# FE_Channel.net
KiCad netlist of a schematic drawn in Altium Designer
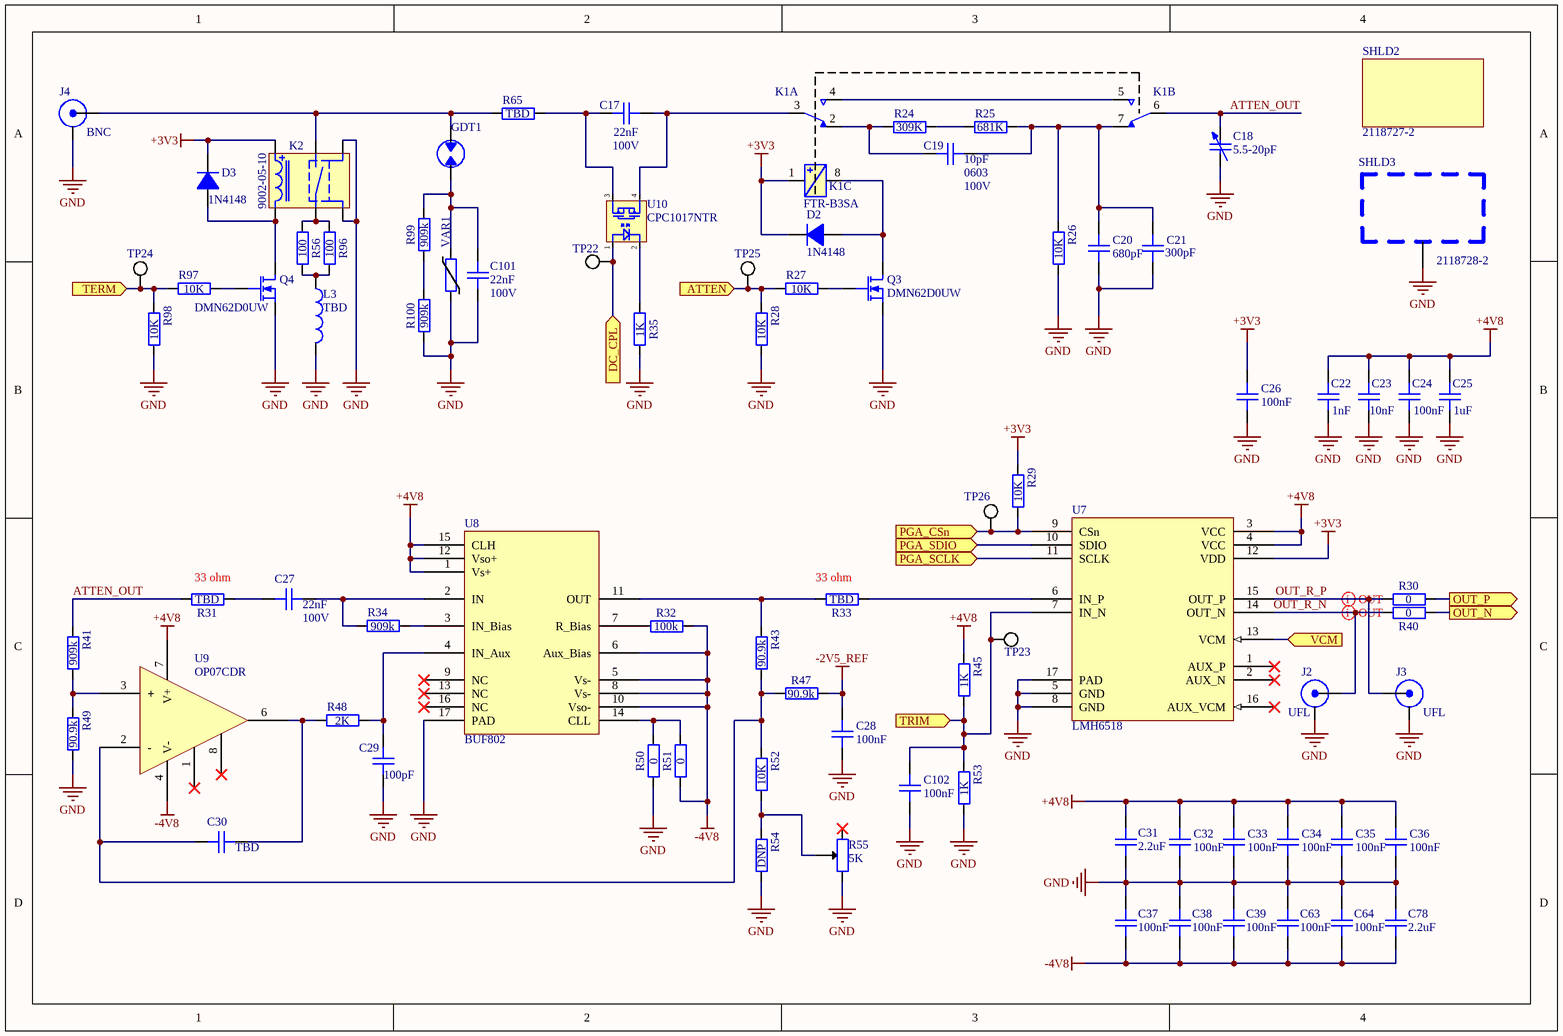
[diagram p0: FE_Channel.SchDoc]

(export (version "E")
  (design (tool "Eeschema 10.0.6"))
  (components
    (comp (ref "C17")
      (value "22nF")
      (footprint "GEN_C_0603")
      (fields (field (name "VOLTAGE RATING") "100V"))
      (libsource (lib "DSO") (part "CAP 22nF 100V X7R 0603"))
    )
    (comp (ref "C18")
      (value "5.5-20pF")
      (footprint "EW_TRIMCAP")
      (libsource (lib "DSO") (part "CAP TRIMMER 5.5-20PF 500V"))
    )
    (comp (ref "C19")
      (value "10pF")
      (footprint "GEN_C_0603")
      (fields (field (name "PACKAGE") "0603") (field (name "VOLTAGE RATING") "100V"))
      (libsource (lib "DSO") (part "CAP 10pF 100V C0G 0603"))
    )
    (comp (ref "C20")
      (value "680pF")
      (footprint "GEN_C_0402")
      (libsource (lib "DSO") (part "CAP 680pF 50V C0G 0402"))
    )
    (comp (ref "C21")
      (value "300pF")
      (footprint "GEN_C_0402")
      (libsource (lib "DSO") (part "CAP 300pF 50V C0G 0402"))
    )
    (comp (ref "C22")
      (value "1nF")
      (footprint "GEN_C_0402")
      (libsource (lib "DSO") (part "CAP 1nF 50V C0G 0402"))
    )
    (comp (ref "C23")
      (value "10nF")
      (footprint "GEN_C_0402")
      (libsource (lib "DSO") (part "CAP 10nF 50V X7R 0402"))
    )
    (comp (ref "C24")
      (value "100nF")
      (footprint "GEN_C_0402")
      (libsource (lib "DSO") (part "CAP 100nF 16V X7R 0402"))
    )
    (comp (ref "C25")
      (value "1uF")
      (footprint "GEN_C_0402")
      (libsource (lib "DSO") (part "CAP 1uF 25V X5R 0402"))
    )
    (comp (ref "C26")
      (value "100nF")
      (footprint "GEN_C_0402")
      (libsource (lib "DSO") (part "CAP 100nF 16V X7R 0402"))
    )
    (comp (ref "C27")
      (value "22nF")
      (footprint "GEN_C_0603")
      (fields (field (name "VOLTAGE RATING") "100V"))
      (libsource (lib "DSO") (part "CAP 22nF 100V X7R 0603"))
    )
    (comp (ref "C28")
      (value "100nF")
      (footprint "GEN_C_0402")
      (libsource (lib "DSO") (part "CAP 100nF 16V X7R 0402"))
    )
    (comp (ref "C29")
      (value "100pF")
      (footprint "GEN_C_0402")
      (libsource (lib "DSO") (part "CAP 100pF 50V C0G 0402"))
    )
    (comp (ref "C30") (value "TBD") (footprint "GEN_C_0402") (libsource (lib "DSO") (part "CAP TBD 0402")))
    (comp (ref "C31")
      (value "2.2uF")
      (footprint "GEN_C_0402")
      (libsource (lib "DSO") (part "CAP 2.2uF 10V X5R 0402"))
    )
    (comp (ref "C32")
      (value "100nF")
      (footprint "GEN_C_0402")
      (libsource (lib "DSO") (part "CAP 100nF 16V X7R 0402"))
    )
    (comp (ref "C33")
      (value "100nF")
      (footprint "GEN_C_0402")
      (libsource (lib "DSO") (part "CAP 100nF 16V X7R 0402"))
    )
    (comp (ref "C34")
      (value "100nF")
      (footprint "GEN_C_0402")
      (libsource (lib "DSO") (part "CAP 100nF 16V X7R 0402"))
    )
    (comp (ref "C35")
      (value "100nF")
      (footprint "GEN_C_0402")
      (libsource (lib "DSO") (part "CAP 100nF 16V X7R 0402"))
    )
    (comp (ref "C36")
      (value "100nF")
      (footprint "GEN_C_0402")
      (libsource (lib "DSO") (part "CAP 100nF 16V X7R 0402"))
    )
    (comp (ref "C37")
      (value "100nF")
      (footprint "GEN_C_0402")
      (libsource (lib "DSO") (part "CAP 100nF 16V X7R 0402"))
    )
    (comp (ref "C38")
      (value "100nF")
      (footprint "GEN_C_0402")
      (libsource (lib "DSO") (part "CAP 100nF 16V X7R 0402"))
    )
    (comp (ref "C39")
      (value "100nF")
      (footprint "GEN_C_0402")
      (libsource (lib "DSO") (part "CAP 100nF 16V X7R 0402"))
    )
    (comp (ref "C63")
      (value "100nF")
      (footprint "GEN_C_0402")
      (libsource (lib "DSO") (part "CAP 100nF 16V X7R 0402"))
    )
    (comp (ref "C64")
      (value "100nF")
      (footprint "GEN_C_0402")
      (libsource (lib "DSO") (part "CAP 100nF 16V X7R 0402"))
    )
    (comp (ref "C78")
      (value "2.2uF")
      (footprint "GEN_C_0402")
      (libsource (lib "DSO") (part "CAP 2.2uF 10V X5R 0402"))
    )
    (comp (ref "C101")
      (value "22nF")
      (footprint "GEN_C_0603")
      (fields (field (name "VOLTAGE RATING") "100V"))
      (libsource (lib "DSO") (part "CAP 22nF 100V X7R 0603"))
    )
    (comp (ref "C102")
      (value "100nF")
      (footprint "GEN_C_0402")
      (libsource (lib "DSO") (part "CAP 100nF 16V X7R 0402"))
    )
    (comp (ref "D2") (value "1N4148") (footprint "GEN_SOD_323") (libsource (lib "DSO") (part "DIODE 1N4148")))
    (comp (ref "D3") (value "1N4148") (footprint "GEN_SOD_323") (libsource (lib "DSO") (part "DIODE 1N4148")))
    (comp (ref "GDT1")
      (value "4532-075-LF")
      (footprint "BOU_2051")
      (libsource (lib "DSO") (part "GDT 75V 1812"))
    )
    (comp (ref "J2") (value "UFL") (footprint "TE_2334884-1") (libsource (lib "DSO") (part "UFL Jack SMD")))
    (comp (ref "J3") (value "UFL") (footprint "TE_2334884-1") (libsource (lib "DSO") (part "UFL Jack SMD")))
    (comp (ref "J4") (value "BNC") (footprint "MOL_0731000105") (libsource (lib "DSO") (part "BNC JACK R/A")))
    (comp (ref "K1")
      (value "FTR-B3SA")
      (footprint "FUJ_FTR-B3SA")
      (libsource (lib "") (part "RELAY DPDT-NO FTR-B3SA_1"))
    )
    (comp (ref "K2")
      (value "9002-05-10")
      (footprint "COTO_9002-05-10")
      (libsource (lib "DSO") (part "RELAY RF SPST-NO 9002-05-10"))
    )
    (comp (ref "L3") (value "TBD") (footprint "GEN_L_0402") (libsource (lib "DSO") (part "IND TBD 0402")))
    (comp (ref "Q3")
      (value "DMN62D0UW")
      (footprint "GEN_SOT_323")
      (libsource (lib "DSO") (part "NMOS DMN62D0UW"))
    )
    (comp (ref "Q4")
      (value "DMN62D0UW")
      (footprint "GEN_SOT_323")
      (libsource (lib "DSO") (part "NMOS DMN62D0UW"))
    )
    (comp (ref "R24")
      (value "309K")
      (footprint "GEN_R_0402")
      (fields (field (name "TOLERANCE") "1%"))
      (libsource (lib "DSO") (part "RES 309K OHM 1% 1/16W 0402"))
    )
    (comp (ref "R25")
      (value "681K")
      (footprint "GEN_R_0402")
      (fields (field (name "TOLERANCE") "1%"))
      (libsource (lib "DSO") (part "RES 681K OHM 1% 1/16W 0402"))
    )
    (comp (ref "R26")
      (value "10K")
      (footprint "GEN_R_0402")
      (fields (field (name "TOLERANCE") "1%"))
      (libsource (lib "DSO") (part "RES 10K OHM 1% 1/10W 0402"))
    )
    (comp (ref "R27")
      (value "10K")
      (footprint "GEN_R_0402")
      (fields (field (name "TOLERANCE") "1%"))
      (libsource (lib "") (part "RES 10K OHM 1% 1/10W 0402_1"))
    )
    (comp (ref "R28")
      (value "10K")
      (footprint "GEN_R_0402")
      (fields (field (name "TOLERANCE") "1%"))
      (libsource (lib "DSO") (part "RES 10K OHM 1% 1/10W 0402"))
    )
    (comp (ref "R29")
      (value "10K")
      (footprint "GEN_R_0402")
      (fields (field (name "TOLERANCE") "1%"))
      (libsource (lib "DSO") (part "RES 10K OHM 1% 1/10W 0402"))
    )
    (comp (ref "R30")
      (value "0")
      (footprint "GEN_R_0402")
      (libsource (lib "DSO") (part "RES 0 OHM 1/16W 0402"))
    )
    (comp (ref "R31")
      (value "TBD")
      (footprint "GEN_R_0402")
      (fields (field (name "TOLERANCE") "1%"))
      (libsource (lib "DSO") (part "RES TBD 0402"))
    )
    (comp (ref "R32")
      (value "100k")
      (footprint "GEN_R_0402")
      (fields (field (name "TOLERANCE") "1%"))
      (libsource (lib "DSO") (part "RES 100K OHM 1% 1/10W 0402"))
    )
    (comp (ref "R33")
      (value "TBD")
      (footprint "GEN_R_0402")
      (fields (field (name "TOLERANCE") "1%"))
      (libsource (lib "DSO") (part "RES TBD 0402"))
    )
    (comp (ref "R34")
      (value "909k")
      (footprint "GEN_R_0402")
      (fields (field (name "TOLERANCE") "1%"))
      (libsource (lib "") (part "RES 909K OHM 1% 1/16W 0402_1"))
    )
    (comp (ref "R35")
      (value "1K")
      (footprint "GEN_R_0402")
      (fields (field (name "TOLERANCE") "1%"))
      (libsource (lib "DSO") (part "RES 1K OHM 1% 1/10W 0402"))
    )
    (comp (ref "R40")
      (value "0")
      (footprint "GEN_R_0402")
      (libsource (lib "DSO") (part "RES 0 OHM 1/16W 0402"))
    )
    (comp (ref "R41")
      (value "909k")
      (footprint "GEN_R_0402")
      (fields (field (name "TOLERANCE") "1%"))
      (libsource (lib "DSO") (part "RES 909K OHM 1% 1/16W 0402"))
    )
    (comp (ref "R43")
      (value "90.9k")
      (footprint "GEN_R_0402")
      (fields (field (name "TOLERANCE") "1%"))
      (libsource (lib "") (part "RES 90.9K OHM 1% 1/16W 0402_1"))
    )
    (comp (ref "R45")
      (value "1K")
      (footprint "GEN_R_0402")
      (fields (field (name "TOLERANCE") "1%"))
      (libsource (lib "") (part "RES 1K OHM 1% 1/10W 0402_1"))
    )
    (comp (ref "R47")
      (value "90.9k")
      (footprint "GEN_R_0402")
      (fields (field (name "TOLERANCE") "1%"))
      (libsource (lib "DSO") (part "RES 90.9K OHM 1% 1/16W 0402"))
    )
    (comp (ref "R48")
      (value "2K")
      (footprint "GEN_R_0402")
      (fields (field (name "TOLERANCE") "1%"))
      (libsource (lib "DSO") (part "RES 2K OHM 1% 1/16W 0402"))
    )
    (comp (ref "R49")
      (value "90.9k")
      (footprint "GEN_R_0402")
      (fields (field (name "TOLERANCE") "1%"))
      (libsource (lib "") (part "RES 90.9K OHM 1% 1/16W 0402_1"))
    )
    (comp (ref "R50")
      (value "0")
      (footprint "GEN_R_0402")
      (libsource (lib "") (part "RES 0 OHM 1/16W 0402_1"))
    )
    (comp (ref "R51")
      (value "0")
      (footprint "GEN_R_0402")
      (libsource (lib "") (part "RES 0 OHM 1/16W 0402_1"))
    )
    (comp (ref "R52")
      (value "10K")
      (footprint "GEN_R_0402")
      (fields (field (name "TOLERANCE") "1%"))
      (libsource (lib "DSO") (part "RES 10K OHM 1% 1/10W 0402"))
    )
    (comp (ref "R53")
      (value "1K")
      (footprint "GEN_R_0402")
      (fields (field (name "TOLERANCE") "1%"))
      (libsource (lib "") (part "RES 1K OHM 1% 1/10W 0402_1"))
    )
    (comp (ref "R54")
      (value "DNP")
      (footprint "GEN_R_0402")
      (fields (field (name "TOLERANCE") "1%"))
      (libsource (lib "DSO") (part "RES DNP 0402"))
    )
    (comp (ref "R55")
      (value "5K")
      (footprint "BOU_3mm_POT")
      (fields (field (name "TOLERANCE") "1%"))
      (libsource (lib "DSO") (part "TRIMMER 5K OHM 0.1W J LEAD TOP"))
    )
    (comp (ref "R56")
      (value "100")
      (footprint "GEN_R_0402")
      (fields (field (name "TOLERANCE") "1%"))
      (libsource (lib "DSO") (part "RES 100 OHM 1% 1/10W 0402"))
    )
    (comp (ref "R65") (value "TBD") (footprint "GEN_R_0603") (libsource (lib "DSO") (part "RES TBD 0603")))
    (comp (ref "R96")
      (value "100")
      (footprint "GEN_R_0402")
      (fields (field (name "TOLERANCE") "1%"))
      (libsource (lib "DSO") (part "RES 100 OHM 1% 1/10W 0402"))
    )
    (comp (ref "R97")
      (value "10K")
      (footprint "GEN_R_0402")
      (fields (field (name "TOLERANCE") "1%"))
      (libsource (lib "") (part "RES 10K OHM 1% 1/10W 0402_1"))
    )
    (comp (ref "R98")
      (value "10K")
      (footprint "GEN_R_0402")
      (fields (field (name "TOLERANCE") "1%"))
      (libsource (lib "DSO") (part "RES 10K OHM 1% 1/10W 0402"))
    )
    (comp (ref "R99")
      (value "909k")
      (footprint "GEN_R_0402")
      (fields (field (name "TOLERANCE") "1%"))
      (libsource (lib "DSO") (part "RES 909K OHM 1% 1/16W 0402"))
    )
    (comp (ref "R100")
      (value "909k")
      (footprint "GEN_R_0402")
      (fields (field (name "TOLERANCE") "1%"))
      (libsource (lib "DSO") (part "RES 909K OHM 1% 1/16W 0402"))
    )
    (comp (ref "SHLD2") (value "2118727-2") (libsource (lib "DSO") (part "SHIELD 2118727-2")))
    (comp (ref "SHLD3")
      (value "2118728-2")
      (footprint "TE_2118728-2")
      (libsource (lib "DSO") (part "SHIELD 2118728-2"))
    )
    (comp (ref "TP22") (value "PCB") (footprint "GEN_TP_PCB") (libsource (lib "DSO") (part "TP PCB 1mm")))
    (comp (ref "TP23") (value "PCB") (footprint "GEN_TP_PCB") (libsource (lib "DSO") (part "TP PCB 1mm")))
    (comp (ref "TP24") (value "PCB") (footprint "GEN_TP_PCB") (libsource (lib "DSO") (part "TP PCB 1mm")))
    (comp (ref "TP25") (value "PCB") (footprint "GEN_TP_PCB") (libsource (lib "DSO") (part "TP PCB 1mm")))
    (comp (ref "TP26") (value "PCB") (footprint "GEN_TP_PCB") (libsource (lib "DSO") (part "TP PCB 1mm")))
    (comp (ref "U7")
      (value "LMH6518")
      (footprint "TI_WQFN_RGH0016A")
      (libsource (lib "DSO") (part "IC PGA LMH6518"))
    )
    (comp (ref "U8")
      (value "BUF802")
      (footprint "TI_VQFN_RGT0016C")
      (libsource (lib "DSO") (part "IC BUFFER AMP BUF802"))
    )
    (comp (ref "U9")
      (value "OP07CDR")
      (footprint "TI_SOIC8_D0008A")
      (libsource (lib "DSO") (part "IC OPAMP OP07CDR"))
    )
    (comp (ref "U10")
      (value "CPC1017NTR")
      (footprint "IXY_CPC1017")
      (libsource (lib "DSO") (part "SSR CPC1017NTR"))
    )
    (comp (ref "VAR1")
      (value "ZV40K1210251NIR1HT")
      (footprint "GEN_VAR_1210")
      (libsource (lib "DSO") (part "VARISTOR 68V 250A 1210"))
    )
  )
  (nets
    (net (code "1") (name "+3V3") (class "Default")
      (node (ref "C26") (pin "2") (pinfunction "2_2") (pintype "passive"))
      (node (ref "D2") (pin "1") (pinfunction "K_1") (pintype "passive"))
      (node (ref "D3") (pin "1") (pinfunction "K_1") (pintype "passive"))
      (node (ref "K1") (pin "1") (pinfunction "1_1") (pintype "passive"))
      (node (ref "K2") (pin "2") (pinfunction "2_2") (pintype "passive"))
      (node (ref "R29") (pin "2") (pinfunction "2_2") (pintype "passive"))
      (node (ref "U7") (pin "12") (pinfunction "VDD_12") (pintype "power_in"))
    )
    (net (code "2") (name "+4V8") (class "Default")
      (node (ref "C22") (pin "2") (pinfunction "2_2") (pintype "passive"))
      (node (ref "C23") (pin "2") (pinfunction "2_2") (pintype "passive"))
      (node (ref "C24") (pin "2") (pinfunction "2_2") (pintype "passive"))
      (node (ref "C25") (pin "2") (pinfunction "2_2") (pintype "passive"))
      (node (ref "C31") (pin "2") (pinfunction "2_2") (pintype "passive"))
      (node (ref "C32") (pin "1") (pinfunction "1_1") (pintype "passive"))
      (node (ref "C33") (pin "1") (pinfunction "1_1") (pintype "passive"))
      (node (ref "C34") (pin "1") (pinfunction "1_1") (pintype "passive"))
      (node (ref "C35") (pin "2") (pinfunction "2_2") (pintype "passive"))
      (node (ref "C36") (pin "2") (pinfunction "2_2") (pintype "passive"))
      (node (ref "R45") (pin "2") (pinfunction "2_2") (pintype "passive"))
      (node (ref "U7") (pin "3") (pinfunction "VCC_3") (pintype "power_in"))
      (node (ref "U7") (pin "4") (pinfunction "VCC_4") (pintype "power_in"))
      (node (ref "U8") (pin "1") (pinfunction "Vs+_1") (pintype "passive"))
      (node (ref "U8") (pin "12") (pinfunction "Vso+_12") (pintype "passive"))
      (node (ref "U8") (pin "15") (pinfunction "CLH_15") (pintype "passive"))
      (node (ref "U9") (pin "7") (pinfunction "V+_7") (pintype "passive"))
    )
    (net (code "3") (name "-2V5_REF") (class "Default")
      (node (ref "C28") (pin "1") (pinfunction "1_1") (pintype "passive"))
      (node (ref "R47") (pin "1") (pinfunction "1_1") (pintype "passive"))
    )
    (net (code "4") (name "-4V8") (class "Default")
      (node (ref "C37") (pin "2") (pinfunction "2_2") (pintype "passive"))
      (node (ref "C38") (pin "2") (pinfunction "2_2") (pintype "passive"))
      (node (ref "C39") (pin "1") (pinfunction "1_1") (pintype "passive"))
      (node (ref "C63") (pin "1") (pinfunction "1_1") (pintype "passive"))
      (node (ref "C64") (pin "1") (pinfunction "1_1") (pintype "passive"))
      (node (ref "C78") (pin "2") (pinfunction "2_2") (pintype "passive"))
      (node (ref "R32") (pin "2") (pinfunction "2_2") (pintype "passive"))
      (node (ref "R51") (pin "1") (pinfunction "1_1") (pintype "passive"))
      (node (ref "U8") (pin "10") (pinfunction "Vso-_10") (pintype "passive"))
      (node (ref "U8") (pin "5") (pinfunction "Vs-_5") (pintype "passive"))
      (node (ref "U8") (pin "6") (pinfunction "Aux_Bias_6") (pintype "passive"))
      (node (ref "U8") (pin "8") (pinfunction "Vs-_8") (pintype "passive"))
      (node (ref "U9") (pin "4") (pinfunction "V-_4") (pintype "passive"))
    )
    (net (code "5") (name "/ATTEN") (class "Default")
      (node (ref "R27") (pin "2") (pinfunction "2_2") (pintype "passive"))
      (node (ref "R28") (pin "2") (pinfunction "2_2") (pintype "passive"))
      (node (ref "TP25") (pin "1") (pinfunction "1_1") (pintype "passive"))
    )
    (net (code "6") (name "/ATTEN_OUT") (class "Default")
      (node (ref "C18") (pin "1") (pinfunction "1_1") (pintype "passive"))
      (node (ref "K1") (pin "6") (pinfunction "6_6") (pintype "passive"))
      (node (ref "R31") (pin "1") (pinfunction "1_1") (pintype "passive"))
      (node (ref "R41") (pin "2") (pinfunction "2_2") (pintype "passive"))
    )
    (net (code "7") (name "/DC_CPL") (class "Default")
      (node (ref "TP22") (pin "1") (pinfunction "1_1") (pintype "passive"))
      (node (ref "U10") (pin "1") (pinfunction "1_1") (pintype "passive"))
    )
    (net (code "8") (name "/OUT_N") (class "Default")
      (node (ref "R40") (pin "2") (pinfunction "2_2") (pintype "passive"))
    )
    (net (code "9") (name "/OUT_P") (class "Default")
      (node (ref "R30") (pin "2") (pinfunction "2_2") (pintype "passive"))
    )
    (net (code "10") (name "/OUT_R_N") (class "Default")
      (node (ref "J2") (pin "1") (pinfunction "Signal_1") (pintype "passive"))
      (node (ref "R40") (pin "1") (pinfunction "1_1") (pintype "passive"))
      (node (ref "U7") (pin "14") (pinfunction "OUT_N_14") (pintype "passive"))
    )
    (net (code "11") (name "/OUT_R_P") (class "Default")
      (node (ref "J3") (pin "1") (pinfunction "Signal_1") (pintype "passive"))
      (node (ref "R30") (pin "1") (pinfunction "1_1") (pintype "passive"))
      (node (ref "U7") (pin "15") (pinfunction "OUT_P_15") (pintype "passive"))
    )
    (net (code "12") (name "/PGA_CSn") (class "Default")
      (node (ref "R29") (pin "1") (pinfunction "1_1") (pintype "passive"))
      (node (ref "TP26") (pin "1") (pinfunction "1_1") (pintype "passive"))
      (node (ref "U7") (pin "9") (pinfunction "CSn_9") (pintype "passive"))
    )
    (net (code "13") (name "/PGA_SCLK") (class "Default")
      (node (ref "U7") (pin "11") (pinfunction "SCLK_11") (pintype "passive"))
    )
    (net (code "14") (name "/PGA_SDIO") (class "Default")
      (node (ref "U7") (pin "10") (pinfunction "SDIO_10") (pintype "passive"))
    )
    (net (code "15") (name "/TERM") (class "Default")
      (node (ref "R97") (pin "2") (pinfunction "2_2") (pintype "passive"))
      (node (ref "R98") (pin "2") (pinfunction "2_2") (pintype "passive"))
      (node (ref "TP24") (pin "1") (pinfunction "1_1") (pintype "passive"))
    )
    (net (code "16") (name "/TRIM") (class "Default")
      (node (ref "C102") (pin "1") (pinfunction "1_1") (pintype "passive"))
      (node (ref "R45") (pin "1") (pinfunction "1_1") (pintype "passive"))
      (node (ref "R53") (pin "2") (pinfunction "2_2") (pintype "passive"))
      (node (ref "TP23") (pin "1") (pinfunction "1_1") (pintype "passive"))
      (node (ref "U7") (pin "7") (pinfunction "IN_N_7") (pintype "passive"))
    )
    (net (code "17") (name "/VCM") (class "Default")
      (node (ref "U7") (pin "13") (pinfunction "VCM_13") (pintype "input"))
    )
    (net (code "18") (name "GND") (class "Default")
      (node (ref "C101") (pin "2") (pinfunction "2_2") (pintype "passive"))
      (node (ref "C102") (pin "2") (pinfunction "2_2") (pintype "passive"))
      (node (ref "C18") (pin "2") (pinfunction "2_2") (pintype "passive"))
      (node (ref "C20") (pin "1") (pinfunction "1_1") (pintype "passive"))
      (node (ref "C21") (pin "1") (pinfunction "1_1") (pintype "passive"))
      (node (ref "C22") (pin "1") (pinfunction "1_1") (pintype "passive"))
      (node (ref "C23") (pin "1") (pinfunction "1_1") (pintype "passive"))
      (node (ref "C24") (pin "1") (pinfunction "1_1") (pintype "passive"))
      (node (ref "C25") (pin "1") (pinfunction "1_1") (pintype "passive"))
      (node (ref "C26") (pin "1") (pinfunction "1_1") (pintype "passive"))
      (node (ref "C28") (pin "2") (pinfunction "2_2") (pintype "passive"))
      (node (ref "C29") (pin "1") (pinfunction "1_1") (pintype "passive"))
      (node (ref "C31") (pin "1") (pinfunction "1_1") (pintype "passive"))
      (node (ref "C32") (pin "2") (pinfunction "2_2") (pintype "passive"))
      (node (ref "C33") (pin "2") (pinfunction "2_2") (pintype "passive"))
      (node (ref "C34") (pin "2") (pinfunction "2_2") (pintype "passive"))
      (node (ref "C35") (pin "1") (pinfunction "1_1") (pintype "passive"))
      (node (ref "C36") (pin "1") (pinfunction "1_1") (pintype "passive"))
      (node (ref "C37") (pin "1") (pinfunction "1_1") (pintype "passive"))
      (node (ref "C38") (pin "1") (pinfunction "1_1") (pintype "passive"))
      (node (ref "C39") (pin "2") (pinfunction "2_2") (pintype "passive"))
      (node (ref "C63") (pin "2") (pinfunction "2_2") (pintype "passive"))
      (node (ref "C64") (pin "2") (pinfunction "2_2") (pintype "passive"))
      (node (ref "C78") (pin "1") (pinfunction "1_1") (pintype "passive"))
      (node (ref "J2") (pin "2") (pinfunction "SHIELD_2") (pintype "passive"))
      (node (ref "J3") (pin "2") (pinfunction "SHIELD_2") (pintype "passive"))
      (node (ref "J4") (pin "2") (pinfunction "SHIELD_2") (pintype "passive"))
      (node (ref "K2") (pin "5") (pinfunction "5_5") (pintype "passive"))
      (node (ref "K2") (pin "6") (pinfunction "6_6") (pintype "passive"))
      (node (ref "L3") (pin "2") (pinfunction "2_2") (pintype "passive"))
      (node (ref "Q3") (pin "3") (pinfunction "S_3") (pintype "passive"))
      (node (ref "Q4") (pin "3") (pinfunction "S_3") (pintype "passive"))
      (node (ref "R100") (pin "1") (pinfunction "1_1") (pintype "passive"))
      (node (ref "R26") (pin "1") (pinfunction "1_1") (pintype "passive"))
      (node (ref "R28") (pin "1") (pinfunction "1_1") (pintype "passive"))
      (node (ref "R35") (pin "1") (pinfunction "1_1") (pintype "passive"))
      (node (ref "R49") (pin "1") (pinfunction "1_1") (pintype "passive"))
      (node (ref "R50") (pin "1") (pinfunction "1_1") (pintype "passive"))
      (node (ref "R53") (pin "1") (pinfunction "1_1") (pintype "passive"))
      (node (ref "R54") (pin "1") (pinfunction "1_1") (pintype "passive"))
      (node (ref "R55") (pin "3") (pinfunction "3_3") (pintype "passive"))
      (node (ref "R98") (pin "1") (pinfunction "1_1") (pintype "passive"))
      (node (ref "SHLD3") (pin "1") (pinfunction "1_1") (pintype "passive"))
      (node (ref "U7") (pin "17") (pinfunction "PAD_17") (pintype "power_in"))
      (node (ref "U7") (pin "5") (pinfunction "GND_5") (pintype "power_in"))
      (node (ref "U7") (pin "8") (pinfunction "GND_8") (pintype "power_in"))
      (node (ref "U8") (pin "17") (pinfunction "PAD_17") (pintype "passive"))
      (node (ref "VAR1") (pin "1") (pinfunction "1_1") (pintype "passive"))
    )
    (net (code "19") (name "Net-(C17-Pad1)") (class "Default")
      (node (ref "C17") (pin "1") (pinfunction "1_1") (pintype "passive"))
      (node (ref "K1") (pin "3") (pinfunction "3_3") (pintype "passive"))
      (node (ref "U10") (pin "4") (pinfunction "4_4") (pintype "passive"))
    )
    (net (code "20") (name "Net-(C17-Pad2)") (class "Default")
      (node (ref "C17") (pin "2") (pinfunction "2_2") (pintype "passive"))
      (node (ref "R65") (pin "2") (pinfunction "2_2") (pintype "passive"))
      (node (ref "U10") (pin "3") (pinfunction "3_3") (pintype "passive"))
    )
    (net (code "21") (name "Net-(C19-Pad1)") (class "Default")
      (node (ref "C19") (pin "1") (pinfunction "1_1") (pintype "passive"))
      (node (ref "C20") (pin "2") (pinfunction "2_2") (pintype "passive"))
      (node (ref "C21") (pin "2") (pinfunction "2_2") (pintype "passive"))
      (node (ref "K1") (pin "7") (pinfunction "7_7") (pintype "passive"))
      (node (ref "R25") (pin "2") (pinfunction "2_2") (pintype "passive"))
      (node (ref "R26") (pin "2") (pinfunction "2_2") (pintype "passive"))
    )
    (net (code "22") (name "Net-(C19-Pad2)") (class "Default")
      (node (ref "C19") (pin "2") (pinfunction "2_2") (pintype "passive"))
      (node (ref "K1") (pin "2") (pinfunction "2_2") (pintype "passive"))
      (node (ref "R24") (pin "1") (pinfunction "1_1") (pintype "passive"))
    )
    (net (code "23") (name "Net-(C27-Pad2)") (class "Default")
      (node (ref "C27") (pin "2") (pinfunction "2_2") (pintype "passive"))
      (node (ref "R31") (pin "2") (pinfunction "2_2") (pintype "passive"))
    )
    (net (code "24") (name "Net-(C101-Pad1)") (class "Default")
      (node (ref "C101") (pin "1") (pinfunction "1_1") (pintype "passive"))
      (node (ref "GDT1") (pin "2") (pinfunction "2_2") (pintype "passive"))
      (node (ref "R99") (pin "2") (pinfunction "2_2") (pintype "passive"))
      (node (ref "VAR1") (pin "2") (pinfunction "2_2") (pintype "passive"))
    )
    (net (code "25") (name "Net-(D2-A)") (class "Default")
      (node (ref "D2") (pin "2") (pinfunction "A_2") (pintype "passive"))
      (node (ref "K1") (pin "8") (pinfunction "8_8") (pintype "passive"))
      (node (ref "Q3") (pin "1") (pinfunction "D_1") (pintype "passive"))
    )
    (net (code "26") (name "Net-(D3-A)") (class "Default")
      (node (ref "D3") (pin "2") (pinfunction "A_2") (pintype "passive"))
      (node (ref "K2") (pin "3") (pinfunction "3_3") (pintype "passive"))
      (node (ref "Q4") (pin "1") (pinfunction "D_1") (pintype "passive"))
    )
    (net (code "27") (name "Net-(J4-Signal)") (class "Default")
      (node (ref "GDT1") (pin "1") (pinfunction "1_1") (pintype "passive"))
      (node (ref "J4") (pin "1") (pinfunction "Signal_1") (pintype "passive"))
      (node (ref "K2") (pin "1") (pinfunction "1_1") (pintype "passive"))
      (node (ref "R65") (pin "1") (pinfunction "1_1") (pintype "passive"))
    )
    (net (code "28") (name "Net-(K1-Pad4)") (class "Default")
      (node (ref "K1") (pin "4") (pinfunction "4_4") (pintype "passive"))
      (node (ref "K1") (pin "5") (pinfunction "5_5") (pintype "passive"))
    )
    (net (code "29") (name "Net-(K2-Pad4)") (class "Default")
      (node (ref "K2") (pin "4") (pinfunction "4_4") (pintype "passive"))
      (node (ref "R56") (pin "2") (pinfunction "2_2") (pintype "passive"))
      (node (ref "R96") (pin "2") (pinfunction "2_2") (pintype "passive"))
    )
    (net (code "30") (name "Net-(L3-Pad1)") (class "Default")
      (node (ref "L3") (pin "1") (pinfunction "1_1") (pintype "passive"))
      (node (ref "R56") (pin "1") (pinfunction "1_1") (pintype "passive"))
      (node (ref "R96") (pin "1") (pinfunction "1_1") (pintype "passive"))
    )
    (net (code "31") (name "Net-(Q3-G)") (class "Default")
      (node (ref "Q3") (pin "2") (pinfunction "G_2") (pintype "passive"))
      (node (ref "R27") (pin "1") (pinfunction "1_1") (pintype "passive"))
    )
    (net (code "32") (name "Net-(Q4-G)") (class "Default")
      (node (ref "Q4") (pin "2") (pinfunction "G_2") (pintype "passive"))
      (node (ref "R97") (pin "1") (pinfunction "1_1") (pintype "passive"))
    )
    (net (code "33") (name "Net-(R24-Pad2)") (class "Default")
      (node (ref "R24") (pin "2") (pinfunction "2_2") (pintype "passive"))
      (node (ref "R25") (pin "1") (pinfunction "1_1") (pintype "passive"))
    )
    (net (code "34") (name "Net-(R35-Pad2)") (class "Default")
      (node (ref "R35") (pin "2") (pinfunction "2_2") (pintype "passive"))
      (node (ref "U10") (pin "2") (pinfunction "2_2") (pintype "passive"))
    )
    (net (code "35") (name "Net-(R52-Pad1)") (class "Default")
      (node (ref "R52") (pin "1") (pinfunction "1_1") (pintype "passive"))
      (node (ref "R54") (pin "2") (pinfunction "2_2") (pintype "passive"))
      (node (ref "R55") (pin "2") (pinfunction "2_2") (pintype "passive"))
    )
    (net (code "36") (name "Net-(R100-Pad2)") (class "Default")
      (node (ref "R100") (pin "2") (pinfunction "2_2") (pintype "passive"))
      (node (ref "R99") (pin "1") (pinfunction "1_1") (pintype "passive"))
    )
    (net (code "37") (name "Net-(U7-IN_P)") (class "Default")
      (node (ref "R33") (pin "2") (pinfunction "2_2") (pintype "passive"))
      (node (ref "U7") (pin "6") (pinfunction "IN_P_6") (pintype "passive"))
    )
    (net (code "38") (name "Net-(U8-CLL)") (class "Default")
      (node (ref "R50") (pin "2") (pinfunction "2_2") (pintype "passive"))
      (node (ref "R51") (pin "2") (pinfunction "2_2") (pintype "passive"))
      (node (ref "U8") (pin "14") (pinfunction "CLL_14") (pintype "passive"))
    )
    (net (code "39") (name "Net-(U8-IN)") (class "Default")
      (node (ref "C27") (pin "1") (pinfunction "1_1") (pintype "passive"))
      (node (ref "R34") (pin "2") (pinfunction "2_2") (pintype "passive"))
      (node (ref "U8") (pin "2") (pinfunction "IN_2") (pintype "passive"))
    )
    (net (code "40") (name "Net-(U8-IN_Aux)") (class "Default")
      (node (ref "C29") (pin "2") (pinfunction "2_2") (pintype "passive"))
      (node (ref "R48") (pin "1") (pinfunction "1_1") (pintype "passive"))
      (node (ref "U8") (pin "4") (pinfunction "IN_Aux_4") (pintype "passive"))
    )
    (net (code "41") (name "Net-(U8-IN_Bias)") (class "Default")
      (node (ref "R34") (pin "1") (pinfunction "1_1") (pintype "passive"))
      (node (ref "U8") (pin "3") (pinfunction "IN_Bias_3") (pintype "passive"))
    )
    (net (code "42") (name "Net-(U8-OUT)") (class "Default")
      (node (ref "R33") (pin "1") (pinfunction "1_1") (pintype "passive"))
      (node (ref "R43") (pin "2") (pinfunction "2_2") (pintype "passive"))
      (node (ref "U8") (pin "11") (pinfunction "OUT_11") (pintype "passive"))
    )
    (net (code "43") (name "Net-(U8-R_Bias)") (class "Default")
      (node (ref "R32") (pin "1") (pinfunction "1_1") (pintype "passive"))
      (node (ref "U8") (pin "7") (pinfunction "R_Bias_7") (pintype "passive"))
    )
    (net (code "44") (name "Net-(U9-+)") (class "Default")
      (node (ref "R41") (pin "1") (pinfunction "1_1") (pintype "passive"))
      (node (ref "R49") (pin "2") (pinfunction "2_2") (pintype "passive"))
      (node (ref "U9") (pin "3") (pinfunction "+_3") (pintype "passive"))
    )
    (net (code "45") (name "Net-(U9--)") (class "Default")
      (node (ref "C30") (pin "2") (pinfunction "2_2") (pintype "passive"))
      (node (ref "R43") (pin "1") (pinfunction "1_1") (pintype "passive"))
      (node (ref "R47") (pin "2") (pinfunction "2_2") (pintype "passive"))
      (node (ref "R52") (pin "2") (pinfunction "2_2") (pintype "passive"))
      (node (ref "U9") (pin "2") (pinfunction "-_2") (pintype "passive"))
    )
    (net (code "46") (name "Net-(U9-OUT)") (class "Default")
      (node (ref "C30") (pin "1") (pinfunction "1_1") (pintype "passive"))
      (node (ref "R48") (pin "2") (pinfunction "2_2") (pintype "passive"))
      (node (ref "U9") (pin "6") (pinfunction "OUT_6") (pintype "passive"))
    )
    (net (code "47") (name "unconnected-(R55-Pad1)") (class "Default")
      (node (ref "R55") (pin "1") (pinfunction "1_1") (pintype "passive+no_connect"))
    )
    (net (code "48") (name "unconnected-(U7-AUX_N-Pad2)") (class "Default")
      (node (ref "U7") (pin "2") (pinfunction "AUX_N_2") (pintype "passive+no_connect"))
    )
    (net (code "49") (name "unconnected-(U7-AUX_P-Pad1)") (class "Default")
      (node (ref "U7") (pin "1") (pinfunction "AUX_P_1") (pintype "passive+no_connect"))
    )
    (net (code "50") (name "unconnected-(U7-AUX_VCM-Pad16)") (class "Default")
      (node (ref "U7") (pin "16") (pinfunction "AUX_VCM_16") (pintype "input+no_connect"))
    )
    (net (code "51") (name "unconnected-(U8-NC-Pad9)") (class "Default")
      (node (ref "U8") (pin "9") (pinfunction "NC_9") (pintype "passive+no_connect"))
    )
    (net (code "52") (name "unconnected-(U8-NC-Pad13)") (class "Default")
      (node (ref "U8") (pin "13") (pinfunction "NC_13") (pintype "passive+no_connect"))
    )
    (net (code "53") (name "unconnected-(U8-NC-Pad16)") (class "Default")
      (node (ref "U8") (pin "16") (pinfunction "NC_16") (pintype "passive+no_connect"))
    )
    (net (code "54") (name "unconnected-(U9-N1-Pad1)") (class "Default")
      (node (ref "U9") (pin "1") (pinfunction "N1_1") (pintype "passive+no_connect"))
    )
    (net (code "55") (name "unconnected-(U9-N2-Pad8)") (class "Default")
      (node (ref "U9") (pin "8") (pinfunction "N2_8") (pintype "passive+no_connect"))
    )
  )
)
